# FP_A_TTypeFBTxs.net
KiCad netlist of a schematic drawn in Altium Designer
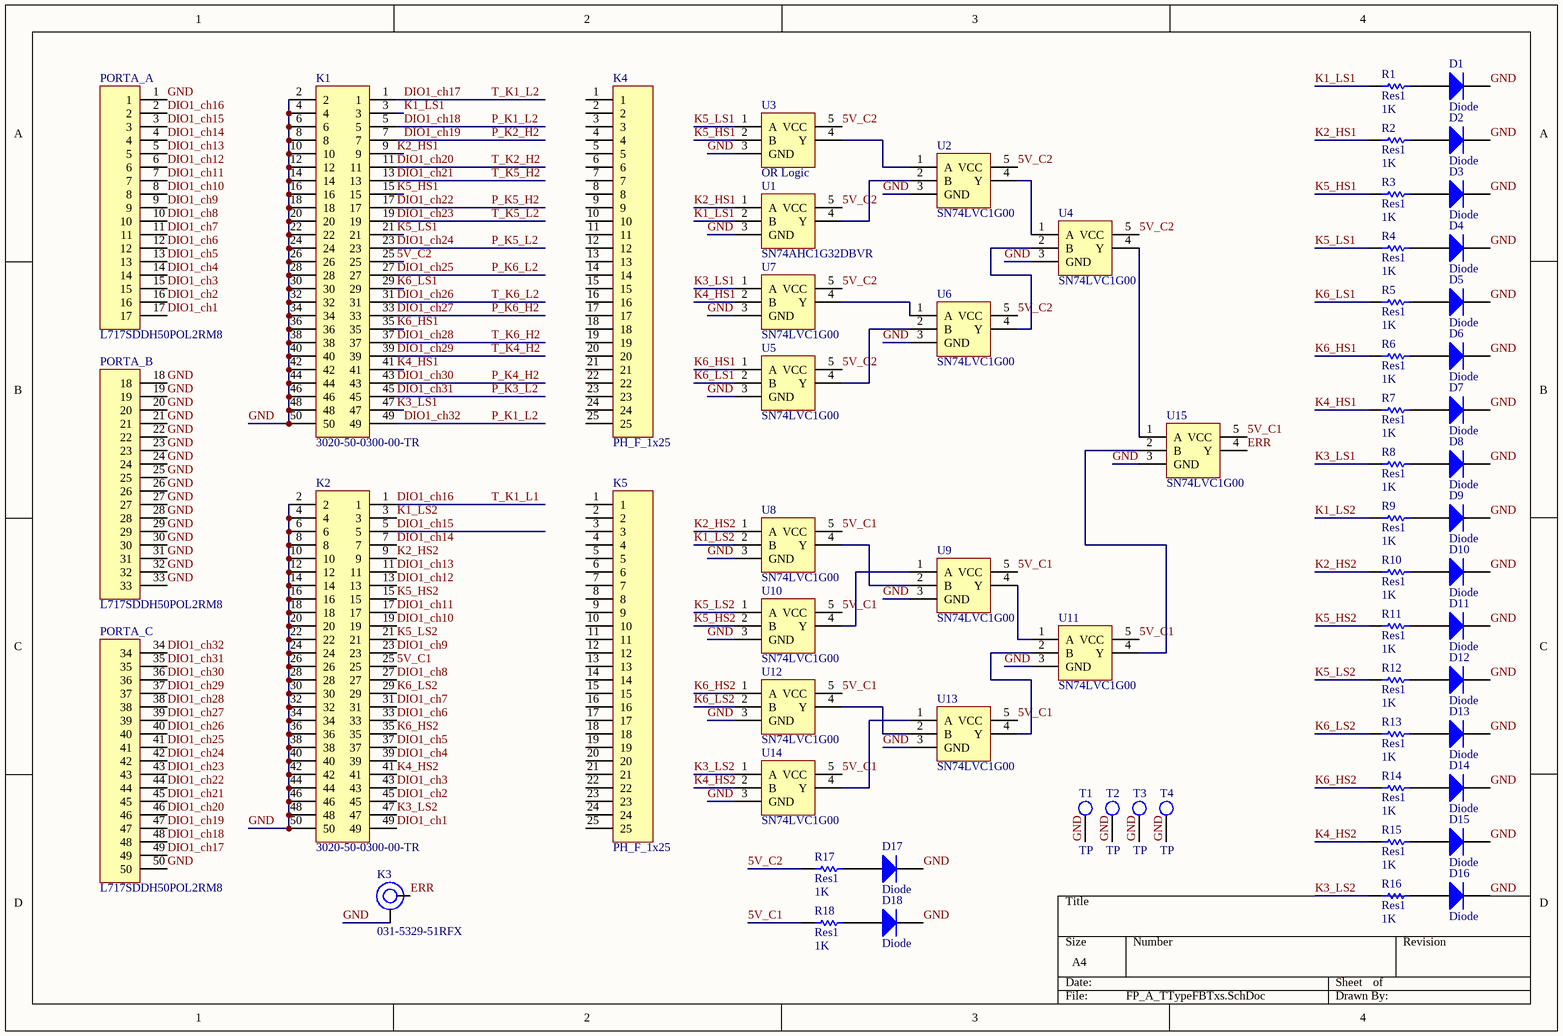
[diagram p0: FP_A_TTypeFBTxs.SchDoc]

(export (version "E")
  (design (tool "Eeschema 10.0.6"))
  (components
    (comp (ref "D1")
      (value "Diode")
      (footprint "0603")
      (description "Default Diode")
      (fields (field (name "PUBLISHER") "Altium Limited"))
      (libsource (lib "Miscellaneous Devices") (part "Diode"))
    )
    (comp (ref "D2")
      (value "Diode")
      (footprint "0603")
      (description "Default Diode")
      (fields (field (name "PUBLISHER") "Altium Limited"))
      (libsource (lib "Miscellaneous Devices") (part "Diode"))
    )
    (comp (ref "D3")
      (value "Diode")
      (footprint "0603")
      (description "Default Diode")
      (fields (field (name "PUBLISHER") "Altium Limited"))
      (libsource (lib "Miscellaneous Devices") (part "Diode"))
    )
    (comp (ref "D4")
      (value "Diode")
      (footprint "0603")
      (description "Default Diode")
      (fields (field (name "PUBLISHER") "Altium Limited"))
      (libsource (lib "Miscellaneous Devices") (part "Diode"))
    )
    (comp (ref "D5")
      (value "Diode")
      (footprint "0603")
      (description "Default Diode")
      (fields (field (name "PUBLISHER") "Altium Limited"))
      (libsource (lib "Miscellaneous Devices") (part "Diode"))
    )
    (comp (ref "D6")
      (value "Diode")
      (footprint "0603")
      (description "Default Diode")
      (fields (field (name "PUBLISHER") "Altium Limited"))
      (libsource (lib "Miscellaneous Devices") (part "Diode"))
    )
    (comp (ref "D7")
      (value "Diode")
      (footprint "0603")
      (description "Default Diode")
      (fields (field (name "PUBLISHER") "Altium Limited"))
      (libsource (lib "Miscellaneous Devices") (part "Diode"))
    )
    (comp (ref "D8")
      (value "Diode")
      (footprint "0603")
      (description "Default Diode")
      (fields (field (name "PUBLISHER") "Altium Limited"))
      (libsource (lib "Miscellaneous Devices") (part "Diode"))
    )
    (comp (ref "D9")
      (value "Diode")
      (footprint "0603")
      (description "Default Diode")
      (fields (field (name "PUBLISHER") "Altium Limited"))
      (libsource (lib "Miscellaneous Devices") (part "Diode"))
    )
    (comp (ref "D10")
      (value "Diode")
      (footprint "0603")
      (description "Default Diode")
      (fields (field (name "PUBLISHER") "Altium Limited"))
      (libsource (lib "Miscellaneous Devices") (part "Diode"))
    )
    (comp (ref "D11")
      (value "Diode")
      (footprint "0603")
      (description "Default Diode")
      (fields (field (name "PUBLISHER") "Altium Limited"))
      (libsource (lib "Miscellaneous Devices") (part "Diode"))
    )
    (comp (ref "D12")
      (value "Diode")
      (footprint "0603")
      (description "Default Diode")
      (fields (field (name "PUBLISHER") "Altium Limited"))
      (libsource (lib "Miscellaneous Devices") (part "Diode"))
    )
    (comp (ref "D13")
      (value "Diode")
      (footprint "0603")
      (description "Default Diode")
      (fields (field (name "PUBLISHER") "Altium Limited"))
      (libsource (lib "Miscellaneous Devices") (part "Diode"))
    )
    (comp (ref "D14")
      (value "Diode")
      (footprint "0603")
      (description "Default Diode")
      (fields (field (name "PUBLISHER") "Altium Limited"))
      (libsource (lib "Miscellaneous Devices") (part "Diode"))
    )
    (comp (ref "D15")
      (value "Diode")
      (footprint "0603")
      (description "Default Diode")
      (fields (field (name "PUBLISHER") "Altium Limited"))
      (libsource (lib "Miscellaneous Devices") (part "Diode"))
    )
    (comp (ref "D16")
      (value "Diode")
      (footprint "0603")
      (description "Default Diode")
      (fields (field (name "PUBLISHER") "Altium Limited"))
      (libsource (lib "Miscellaneous Devices") (part "Diode"))
    )
    (comp (ref "D17")
      (value "Diode")
      (footprint "0603")
      (description "Default Diode")
      (fields (field (name "PUBLISHER") "Altium Limited"))
      (libsource (lib "Miscellaneous Devices") (part "Diode"))
    )
    (comp (ref "D18")
      (value "Diode")
      (footprint "0603")
      (description "Default Diode")
      (fields (field (name "PUBLISHER") "Altium Limited"))
      (libsource (lib "Miscellaneous Devices") (part "Diode"))
    )
    (comp (ref "K1")
      (value "3020-50-0300-00-TR")
      (footprint "IDC_2x50")
      (libsource (lib "Schlib1") (part "3020-50-0300-00-TR"))
    )
    (comp (ref "K2")
      (value "3020-50-0300-00-TR")
      (footprint "IDC_2x50")
      (libsource (lib "Schlib1") (part "3020-50-0300-00-TR"))
    )
    (comp (ref "K3")
      (value "031-5329-51RFX")
      (footprint "BNC_PCB")
      (libsource (lib "Schlib1") (part "031-5329-51RFX"))
    )
    (comp (ref "K4")
      (value "PH_F_1x25")
      (footprint "PH_F_1x25")
      (libsource (lib "Schlib1") (part "PH_F_1x25"))
    )
    (comp (ref "K5")
      (value "PH_F_1x25")
      (footprint "PH_F_1x25")
      (libsource (lib "Schlib1") (part "PH_F_1x25"))
    )
    (comp (ref "PORTA_")
      (value "L717SDDH50POL2RM8")
      (footprint "L717SDDH50POL2RM8")
      (libsource (lib "Schlib1") (part "L717SDDH50POL2RM8"))
    )
    (comp (ref "R1")
      (value "Res1")
      (footprint "0603")
      (description "Resistor")
      (fields (field (name "ALTIUM_VALUE") "1K") (field (name "PUBLISHER") "Altium Limited"))
      (libsource (lib "Miscellaneous Devices") (part "Res1"))
    )
    (comp (ref "R2")
      (value "Res1")
      (footprint "0603")
      (description "Resistor")
      (fields (field (name "ALTIUM_VALUE") "1K") (field (name "PUBLISHER") "Altium Limited"))
      (libsource (lib "Miscellaneous Devices") (part "Res1"))
    )
    (comp (ref "R3")
      (value "Res1")
      (footprint "0603")
      (description "Resistor")
      (fields (field (name "ALTIUM_VALUE") "1K") (field (name "PUBLISHER") "Altium Limited"))
      (libsource (lib "Miscellaneous Devices") (part "Res1"))
    )
    (comp (ref "R4")
      (value "Res1")
      (footprint "0603")
      (description "Resistor")
      (fields (field (name "ALTIUM_VALUE") "1K") (field (name "PUBLISHER") "Altium Limited"))
      (libsource (lib "Miscellaneous Devices") (part "Res1"))
    )
    (comp (ref "R5")
      (value "Res1")
      (footprint "0603")
      (description "Resistor")
      (fields (field (name "ALTIUM_VALUE") "1K") (field (name "PUBLISHER") "Altium Limited"))
      (libsource (lib "Miscellaneous Devices") (part "Res1"))
    )
    (comp (ref "R6")
      (value "Res1")
      (footprint "0603")
      (description "Resistor")
      (fields (field (name "ALTIUM_VALUE") "1K") (field (name "PUBLISHER") "Altium Limited"))
      (libsource (lib "Miscellaneous Devices") (part "Res1"))
    )
    (comp (ref "R7")
      (value "Res1")
      (footprint "0603")
      (description "Resistor")
      (fields (field (name "ALTIUM_VALUE") "1K") (field (name "PUBLISHER") "Altium Limited"))
      (libsource (lib "Miscellaneous Devices") (part "Res1"))
    )
    (comp (ref "R8")
      (value "Res1")
      (footprint "0603")
      (description "Resistor")
      (fields (field (name "ALTIUM_VALUE") "1K") (field (name "PUBLISHER") "Altium Limited"))
      (libsource (lib "Miscellaneous Devices") (part "Res1"))
    )
    (comp (ref "R9")
      (value "Res1")
      (footprint "0603")
      (description "Resistor")
      (fields (field (name "ALTIUM_VALUE") "1K") (field (name "PUBLISHER") "Altium Limited"))
      (libsource (lib "Miscellaneous Devices") (part "Res1"))
    )
    (comp (ref "R10")
      (value "Res1")
      (footprint "0603")
      (description "Resistor")
      (fields (field (name "ALTIUM_VALUE") "1K") (field (name "PUBLISHER") "Altium Limited"))
      (libsource (lib "Miscellaneous Devices") (part "Res1"))
    )
    (comp (ref "R11")
      (value "Res1")
      (footprint "0603")
      (description "Resistor")
      (fields (field (name "ALTIUM_VALUE") "1K") (field (name "PUBLISHER") "Altium Limited"))
      (libsource (lib "Miscellaneous Devices") (part "Res1"))
    )
    (comp (ref "R12")
      (value "Res1")
      (footprint "0603")
      (description "Resistor")
      (fields (field (name "ALTIUM_VALUE") "1K") (field (name "PUBLISHER") "Altium Limited"))
      (libsource (lib "Miscellaneous Devices") (part "Res1"))
    )
    (comp (ref "R13")
      (value "Res1")
      (footprint "0603")
      (description "Resistor")
      (fields (field (name "ALTIUM_VALUE") "1K") (field (name "PUBLISHER") "Altium Limited"))
      (libsource (lib "Miscellaneous Devices") (part "Res1"))
    )
    (comp (ref "R14")
      (value "Res1")
      (footprint "0603")
      (description "Resistor")
      (fields (field (name "ALTIUM_VALUE") "1K") (field (name "PUBLISHER") "Altium Limited"))
      (libsource (lib "Miscellaneous Devices") (part "Res1"))
    )
    (comp (ref "R15")
      (value "Res1")
      (footprint "0603")
      (description "Resistor")
      (fields (field (name "ALTIUM_VALUE") "1K") (field (name "PUBLISHER") "Altium Limited"))
      (libsource (lib "Miscellaneous Devices") (part "Res1"))
    )
    (comp (ref "R16")
      (value "Res1")
      (footprint "0603")
      (description "Resistor")
      (fields (field (name "ALTIUM_VALUE") "1K") (field (name "PUBLISHER") "Altium Limited"))
      (libsource (lib "Miscellaneous Devices") (part "Res1"))
    )
    (comp (ref "R17")
      (value "Res1")
      (footprint "0603")
      (description "Resistor")
      (fields (field (name "ALTIUM_VALUE") "1K") (field (name "PUBLISHER") "Altium Limited"))
      (libsource (lib "Miscellaneous Devices") (part "Res1"))
    )
    (comp (ref "R18")
      (value "Res1")
      (footprint "0603")
      (description "Resistor")
      (fields (field (name "ALTIUM_VALUE") "1K") (field (name "PUBLISHER") "Altium Limited"))
      (libsource (lib "Miscellaneous Devices") (part "Res1"))
    )
    (comp (ref "T1") (value "TP") (footprint "TP") (libsource (lib "Schlib1") (part "TP")))
    (comp (ref "T2") (value "TP") (footprint "TP") (libsource (lib "Schlib1") (part "TP")))
    (comp (ref "T3") (value "TP") (footprint "TP") (libsource (lib "Schlib1") (part "TP")))
    (comp (ref "T4") (value "TP") (footprint "TP") (libsource (lib "Schlib1") (part "TP")))
    (comp (ref "U1")
      (value "SN74AHC1G32DBVR")
      (footprint "sot23")
      (libsource (lib "Schlib1") (part "SN74AHC1G32DBVR"))
    )
    (comp (ref "U2")
      (value "SN74LVC1G00")
      (footprint "sot23")
      (libsource (lib "Schlib1") (part "SN74LVC1G00"))
    )
    (comp (ref "U3")
      (value "OR Logic")
      (footprint "sot23")
      (libsource (lib "Schlib1") (part "SN74AHC1G32DBVR"))
    )
    (comp (ref "U4")
      (value "SN74LVC1G00")
      (footprint "sot23")
      (libsource (lib "Schlib1") (part "SN74LVC1G00"))
    )
    (comp (ref "U5")
      (value "SN74LVC1G00")
      (footprint "sot23")
      (libsource (lib "Schlib1") (part "SN74LVC1G00"))
    )
    (comp (ref "U6")
      (value "SN74LVC1G00")
      (footprint "sot23")
      (libsource (lib "Schlib1") (part "SN74LVC1G00"))
    )
    (comp (ref "U7")
      (value "SN74LVC1G00")
      (footprint "sot23")
      (libsource (lib "Schlib1") (part "SN74LVC1G00"))
    )
    (comp (ref "U8")
      (value "SN74LVC1G00")
      (footprint "sot23")
      (libsource (lib "Schlib1") (part "SN74LVC1G00"))
    )
    (comp (ref "U9")
      (value "SN74LVC1G00")
      (footprint "sot23")
      (libsource (lib "Schlib1") (part "SN74LVC1G00"))
    )
    (comp (ref "U10")
      (value "SN74LVC1G00")
      (footprint "sot23")
      (libsource (lib "Schlib1") (part "SN74LVC1G00"))
    )
    (comp (ref "U11")
      (value "SN74LVC1G00")
      (footprint "sot23")
      (libsource (lib "Schlib1") (part "SN74LVC1G00"))
    )
    (comp (ref "U12")
      (value "SN74LVC1G00")
      (footprint "sot23")
      (libsource (lib "Schlib1") (part "SN74LVC1G00"))
    )
    (comp (ref "U13")
      (value "SN74LVC1G00")
      (footprint "sot23")
      (libsource (lib "Schlib1") (part "SN74LVC1G00"))
    )
    (comp (ref "U14")
      (value "SN74LVC1G00")
      (footprint "sot23")
      (libsource (lib "Schlib1") (part "SN74LVC1G00"))
    )
    (comp (ref "U15")
      (value "SN74LVC1G00")
      (footprint "sot23")
      (libsource (lib "Schlib1") (part "SN74LVC1G00"))
    )
  )
  (nets
    (net (code "1") (name "/5V_C1") (class "Default")
      (node (ref "K2") (pin "25") (pinfunction "25_25") (pintype "passive"))
      (node (ref "R18") (pin "2") (pinfunction "2_2") (pintype "passive"))
      (node (ref "U10") (pin "5") (pinfunction "VCC_5") (pintype "passive"))
      (node (ref "U11") (pin "5") (pinfunction "VCC_5") (pintype "passive"))
      (node (ref "U12") (pin "5") (pinfunction "VCC_5") (pintype "passive"))
      (node (ref "U13") (pin "5") (pinfunction "VCC_5") (pintype "passive"))
      (node (ref "U14") (pin "5") (pinfunction "VCC_5") (pintype "passive"))
      (node (ref "U15") (pin "5") (pinfunction "VCC_5") (pintype "passive"))
      (node (ref "U8") (pin "5") (pinfunction "VCC_5") (pintype "passive"))
      (node (ref "U9") (pin "5") (pinfunction "VCC_5") (pintype "passive"))
    )
    (net (code "2") (name "/5V_C2") (class "Default")
      (node (ref "K1") (pin "25") (pinfunction "25_25") (pintype "passive"))
      (node (ref "R17") (pin "2") (pinfunction "2_2") (pintype "passive"))
      (node (ref "U1") (pin "5") (pinfunction "VCC_5") (pintype "passive"))
      (node (ref "U2") (pin "5") (pinfunction "VCC_5") (pintype "passive"))
      (node (ref "U3") (pin "5") (pinfunction "VCC_5") (pintype "passive"))
      (node (ref "U4") (pin "5") (pinfunction "VCC_5") (pintype "passive"))
      (node (ref "U5") (pin "5") (pinfunction "VCC_5") (pintype "passive"))
      (node (ref "U6") (pin "5") (pinfunction "VCC_5") (pintype "passive"))
      (node (ref "U7") (pin "5") (pinfunction "VCC_5") (pintype "passive"))
    )
    (net (code "3") (name "/DIO1_ch1") (class "Default")
      (node (ref "K2") (pin "49") (pinfunction "49_49") (pintype "passive"))
      (node (ref "PORTA_") (pin "17") (pinfunction "17_17") (pintype "passive"))
    )
    (net (code "4") (name "/DIO1_ch2") (class "Default")
      (node (ref "K2") (pin "45") (pinfunction "45_45") (pintype "passive"))
      (node (ref "PORTA_") (pin "16") (pinfunction "16_16") (pintype "passive"))
    )
    (net (code "5") (name "/DIO1_ch3") (class "Default")
      (node (ref "K2") (pin "43") (pinfunction "43_43") (pintype "passive"))
      (node (ref "PORTA_") (pin "15") (pinfunction "15_15") (pintype "passive"))
    )
    (net (code "6") (name "/DIO1_ch4") (class "Default")
      (node (ref "K2") (pin "39") (pinfunction "39_39") (pintype "passive"))
      (node (ref "PORTA_") (pin "14") (pinfunction "14_14") (pintype "passive"))
    )
    (net (code "7") (name "/DIO1_ch5") (class "Default")
      (node (ref "K2") (pin "37") (pinfunction "37_37") (pintype "passive"))
      (node (ref "PORTA_") (pin "13") (pinfunction "13_13") (pintype "passive"))
    )
    (net (code "8") (name "/DIO1_ch6") (class "Default")
      (node (ref "K2") (pin "33") (pinfunction "33_33") (pintype "passive"))
      (node (ref "PORTA_") (pin "12") (pinfunction "12_12") (pintype "passive"))
    )
    (net (code "9") (name "/DIO1_ch7") (class "Default")
      (node (ref "K2") (pin "31") (pinfunction "31_31") (pintype "passive"))
      (node (ref "PORTA_") (pin "11") (pinfunction "11_11") (pintype "passive"))
    )
    (net (code "10") (name "/DIO1_ch8") (class "Default")
      (node (ref "K2") (pin "27") (pinfunction "27_27") (pintype "passive"))
      (node (ref "PORTA_") (pin "10") (pinfunction "10_10") (pintype "passive"))
    )
    (net (code "11") (name "/DIO1_ch9") (class "Default")
      (node (ref "K2") (pin "23") (pinfunction "23_23") (pintype "passive"))
      (node (ref "PORTA_") (pin "9") (pinfunction "9_9") (pintype "passive"))
    )
    (net (code "12") (name "/DIO1_ch10") (class "Default")
      (node (ref "K2") (pin "19") (pinfunction "19_19") (pintype "passive"))
      (node (ref "PORTA_") (pin "8") (pinfunction "8_8") (pintype "passive"))
    )
    (net (code "13") (name "/DIO1_ch11") (class "Default")
      (node (ref "K2") (pin "17") (pinfunction "17_17") (pintype "passive"))
      (node (ref "PORTA_") (pin "7") (pinfunction "7_7") (pintype "passive"))
    )
    (net (code "14") (name "/DIO1_ch12") (class "Default")
      (node (ref "K2") (pin "13") (pinfunction "13_13") (pintype "passive"))
      (node (ref "PORTA_") (pin "6") (pinfunction "6_6") (pintype "passive"))
    )
    (net (code "15") (name "/DIO1_ch13") (class "Default")
      (node (ref "K2") (pin "11") (pinfunction "11_11") (pintype "passive"))
      (node (ref "PORTA_") (pin "5") (pinfunction "5_5") (pintype "passive"))
    )
    (net (code "16") (name "/DIO1_ch14") (class "Default")
      (node (ref "K2") (pin "7") (pinfunction "7_7") (pintype "passive"))
      (node (ref "PORTA_") (pin "4") (pinfunction "4_4") (pintype "passive"))
    )
    (net (code "17") (name "/DIO1_ch15") (class "Default")
      (node (ref "K2") (pin "5") (pinfunction "5_5") (pintype "passive"))
      (node (ref "PORTA_") (pin "3") (pinfunction "3_3") (pintype "passive"))
    )
    (net (code "18") (name "/DIO1_ch16") (class "Default")
      (node (ref "K2") (pin "1") (pinfunction "1_1") (pintype "passive"))
      (node (ref "PORTA_") (pin "2") (pinfunction "2_2") (pintype "passive"))
    )
    (net (code "19") (name "/DIO1_ch17") (class "Default")
      (node (ref "K1") (pin "1") (pinfunction "1_1") (pintype "passive"))
      (node (ref "PORTA_") (pin "49") (pinfunction "49_49") (pintype "passive"))
    )
    (net (code "20") (name "/DIO1_ch18") (class "Default")
      (node (ref "K1") (pin "49") (pinfunction "49_49") (pintype "passive"))
      (node (ref "K1") (pin "5") (pinfunction "5_5") (pintype "passive"))
      (node (ref "PORTA_") (pin "34") (pinfunction "34_34") (pintype "passive"))
      (node (ref "PORTA_") (pin "48") (pinfunction "48_48") (pintype "passive"))
    )
    (net (code "21") (name "/DIO1_ch19") (class "Default")
      (node (ref "K1") (pin "7") (pinfunction "7_7") (pintype "passive"))
      (node (ref "PORTA_") (pin "47") (pinfunction "47_47") (pintype "passive"))
    )
    (net (code "22") (name "/DIO1_ch20") (class "Default")
      (node (ref "K1") (pin "11") (pinfunction "11_11") (pintype "passive"))
      (node (ref "PORTA_") (pin "46") (pinfunction "46_46") (pintype "passive"))
    )
    (net (code "23") (name "/DIO1_ch21") (class "Default")
      (node (ref "K1") (pin "13") (pinfunction "13_13") (pintype "passive"))
      (node (ref "PORTA_") (pin "45") (pinfunction "45_45") (pintype "passive"))
    )
    (net (code "24") (name "/DIO1_ch22") (class "Default")
      (node (ref "K1") (pin "17") (pinfunction "17_17") (pintype "passive"))
      (node (ref "PORTA_") (pin "44") (pinfunction "44_44") (pintype "passive"))
    )
    (net (code "25") (name "/DIO1_ch23") (class "Default")
      (node (ref "K1") (pin "19") (pinfunction "19_19") (pintype "passive"))
      (node (ref "PORTA_") (pin "43") (pinfunction "43_43") (pintype "passive"))
    )
    (net (code "26") (name "/DIO1_ch24") (class "Default")
      (node (ref "K1") (pin "23") (pinfunction "23_23") (pintype "passive"))
      (node (ref "PORTA_") (pin "42") (pinfunction "42_42") (pintype "passive"))
    )
    (net (code "27") (name "/DIO1_ch25") (class "Default")
      (node (ref "K1") (pin "27") (pinfunction "27_27") (pintype "passive"))
      (node (ref "PORTA_") (pin "41") (pinfunction "41_41") (pintype "passive"))
    )
    (net (code "28") (name "/DIO1_ch26") (class "Default")
      (node (ref "K1") (pin "31") (pinfunction "31_31") (pintype "passive"))
      (node (ref "PORTA_") (pin "40") (pinfunction "40_40") (pintype "passive"))
    )
    (net (code "29") (name "/DIO1_ch27") (class "Default")
      (node (ref "K1") (pin "33") (pinfunction "33_33") (pintype "passive"))
      (node (ref "PORTA_") (pin "39") (pinfunction "39_39") (pintype "passive"))
    )
    (net (code "30") (name "/DIO1_ch28") (class "Default")
      (node (ref "K1") (pin "37") (pinfunction "37_37") (pintype "passive"))
      (node (ref "PORTA_") (pin "38") (pinfunction "38_38") (pintype "passive"))
    )
    (net (code "31") (name "/DIO1_ch29") (class "Default")
      (node (ref "K1") (pin "39") (pinfunction "39_39") (pintype "passive"))
      (node (ref "PORTA_") (pin "37") (pinfunction "37_37") (pintype "passive"))
    )
    (net (code "32") (name "/DIO1_ch30") (class "Default")
      (node (ref "K1") (pin "43") (pinfunction "43_43") (pintype "passive"))
      (node (ref "PORTA_") (pin "36") (pinfunction "36_36") (pintype "passive"))
    )
    (net (code "33") (name "/DIO1_ch31") (class "Default")
      (node (ref "K1") (pin "45") (pinfunction "45_45") (pintype "passive"))
      (node (ref "PORTA_") (pin "35") (pinfunction "35_35") (pintype "passive"))
    )
    (net (code "34") (name "/ERR") (class "Default")
      (node (ref "K3") (pin "1") (pinfunction "1_1") (pintype "passive"))
      (node (ref "U15") (pin "4") (pinfunction "Y_4") (pintype "passive"))
    )
    (net (code "35") (name "/GND") (class "Default")
      (node (ref "D1") (pin "2") (pinfunction "K_2") (pintype "passive"))
      (node (ref "D10") (pin "2") (pinfunction "K_2") (pintype "passive"))
      (node (ref "D11") (pin "2") (pinfunction "K_2") (pintype "passive"))
      (node (ref "D12") (pin "2") (pinfunction "K_2") (pintype "passive"))
      (node (ref "D13") (pin "2") (pinfunction "K_2") (pintype "passive"))
      (node (ref "D14") (pin "2") (pinfunction "K_2") (pintype "passive"))
      (node (ref "D15") (pin "2") (pinfunction "K_2") (pintype "passive"))
      (node (ref "D16") (pin "2") (pinfunction "K_2") (pintype "passive"))
      (node (ref "D17") (pin "2") (pinfunction "K_2") (pintype "passive"))
      (node (ref "D18") (pin "2") (pinfunction "K_2") (pintype "passive"))
      (node (ref "D2") (pin "2") (pinfunction "K_2") (pintype "passive"))
      (node (ref "D3") (pin "2") (pinfunction "K_2") (pintype "passive"))
      (node (ref "D4") (pin "2") (pinfunction "K_2") (pintype "passive"))
      (node (ref "D5") (pin "2") (pinfunction "K_2") (pintype "passive"))
      (node (ref "D6") (pin "2") (pinfunction "K_2") (pintype "passive"))
      (node (ref "D7") (pin "2") (pinfunction "K_2") (pintype "passive"))
      (node (ref "D8") (pin "2") (pinfunction "K_2") (pintype "passive"))
      (node (ref "D9") (pin "2") (pinfunction "K_2") (pintype "passive"))
      (node (ref "K1") (pin "10") (pinfunction "10_10") (pintype "passive"))
      (node (ref "K1") (pin "12") (pinfunction "12_12") (pintype "passive"))
      (node (ref "K1") (pin "14") (pinfunction "14_14") (pintype "passive"))
      (node (ref "K1") (pin "16") (pinfunction "16_16") (pintype "passive"))
      (node (ref "K1") (pin "18") (pinfunction "18_18") (pintype "passive"))
      (node (ref "K1") (pin "2") (pinfunction "2_2") (pintype "passive"))
      (node (ref "K1") (pin "20") (pinfunction "20_20") (pintype "passive"))
      (node (ref "K1") (pin "22") (pinfunction "22_22") (pintype "passive"))
      (node (ref "K1") (pin "24") (pinfunction "24_24") (pintype "passive"))
      (node (ref "K1") (pin "26") (pinfunction "26_26") (pintype "passive"))
      (node (ref "K1") (pin "28") (pinfunction "28_28") (pintype "passive"))
      (node (ref "K1") (pin "30") (pinfunction "30_30") (pintype "passive"))
      (node (ref "K1") (pin "32") (pinfunction "32_32") (pintype "passive"))
      (node (ref "K1") (pin "34") (pinfunction "34_34") (pintype "passive"))
      (node (ref "K1") (pin "36") (pinfunction "36_36") (pintype "passive"))
      (node (ref "K1") (pin "38") (pinfunction "38_38") (pintype "passive"))
      (node (ref "K1") (pin "4") (pinfunction "4_4") (pintype "passive"))
      (node (ref "K1") (pin "40") (pinfunction "40_40") (pintype "passive"))
      (node (ref "K1") (pin "42") (pinfunction "42_42") (pintype "passive"))
      (node (ref "K1") (pin "44") (pinfunction "44_44") (pintype "passive"))
      (node (ref "K1") (pin "46") (pinfunction "46_46") (pintype "passive"))
      (node (ref "K1") (pin "48") (pinfunction "48_48") (pintype "passive"))
      (node (ref "K1") (pin "50") (pinfunction "50_50") (pintype "passive"))
      (node (ref "K1") (pin "6") (pinfunction "6_6") (pintype "passive"))
      (node (ref "K1") (pin "8") (pinfunction "8_8") (pintype "passive"))
      (node (ref "K2") (pin "10") (pinfunction "10_10") (pintype "passive"))
      (node (ref "K2") (pin "12") (pinfunction "12_12") (pintype "passive"))
      (node (ref "K2") (pin "14") (pinfunction "14_14") (pintype "passive"))
      (node (ref "K2") (pin "16") (pinfunction "16_16") (pintype "passive"))
      (node (ref "K2") (pin "18") (pinfunction "18_18") (pintype "passive"))
      (node (ref "K2") (pin "2") (pinfunction "2_2") (pintype "passive"))
      (node (ref "K2") (pin "20") (pinfunction "20_20") (pintype "passive"))
      (node (ref "K2") (pin "22") (pinfunction "22_22") (pintype "passive"))
      (node (ref "K2") (pin "24") (pinfunction "24_24") (pintype "passive"))
      (node (ref "K2") (pin "26") (pinfunction "26_26") (pintype "passive"))
      (node (ref "K2") (pin "28") (pinfunction "28_28") (pintype "passive"))
      (node (ref "K2") (pin "30") (pinfunction "30_30") (pintype "passive"))
      (node (ref "K2") (pin "32") (pinfunction "32_32") (pintype "passive"))
      (node (ref "K2") (pin "34") (pinfunction "34_34") (pintype "passive"))
      (node (ref "K2") (pin "36") (pinfunction "36_36") (pintype "passive"))
      (node (ref "K2") (pin "38") (pinfunction "38_38") (pintype "passive"))
      (node (ref "K2") (pin "4") (pinfunction "4_4") (pintype "passive"))
      (node (ref "K2") (pin "40") (pinfunction "40_40") (pintype "passive"))
      (node (ref "K2") (pin "42") (pinfunction "42_42") (pintype "passive"))
      (node (ref "K2") (pin "44") (pinfunction "44_44") (pintype "passive"))
      (node (ref "K2") (pin "46") (pinfunction "46_46") (pintype "passive"))
      (node (ref "K2") (pin "48") (pinfunction "48_48") (pintype "passive"))
      (node (ref "K2") (pin "50") (pinfunction "50_50") (pintype "passive"))
      (node (ref "K2") (pin "6") (pinfunction "6_6") (pintype "passive"))
      (node (ref "K2") (pin "8") (pinfunction "8_8") (pintype "passive"))
      (node (ref "K3") (pin "2") (pinfunction "2_2") (pintype "passive"))
      (node (ref "PORTA_") (pin "1") (pinfunction "1_1") (pintype "passive"))
      (node (ref "PORTA_") (pin "18") (pinfunction "18_18") (pintype "passive"))
      (node (ref "PORTA_") (pin "19") (pinfunction "19_19") (pintype "passive"))
      (node (ref "PORTA_") (pin "20") (pinfunction "20_20") (pintype "passive"))
      (node (ref "PORTA_") (pin "21") (pinfunction "21_21") (pintype "passive"))
      (node (ref "PORTA_") (pin "22") (pinfunction "22_22") (pintype "passive"))
      (node (ref "PORTA_") (pin "23") (pinfunction "23_23") (pintype "passive"))
      (node (ref "PORTA_") (pin "24") (pinfunction "24_24") (pintype "passive"))
      (node (ref "PORTA_") (pin "25") (pinfunction "25_25") (pintype "passive"))
      (node (ref "PORTA_") (pin "26") (pinfunction "26_26") (pintype "passive"))
      (node (ref "PORTA_") (pin "27") (pinfunction "27_27") (pintype "passive"))
      (node (ref "PORTA_") (pin "28") (pinfunction "28_28") (pintype "passive"))
      (node (ref "PORTA_") (pin "29") (pinfunction "29_29") (pintype "passive"))
      (node (ref "PORTA_") (pin "30") (pinfunction "30_30") (pintype "passive"))
      (node (ref "PORTA_") (pin "31") (pinfunction "31_31") (pintype "passive"))
      (node (ref "PORTA_") (pin "32") (pinfunction "32_32") (pintype "passive"))
      (node (ref "PORTA_") (pin "33") (pinfunction "33_33") (pintype "passive"))
      (node (ref "PORTA_") (pin "50") (pinfunction "50_50") (pintype "passive"))
      (node (ref "T1") (pin "1") (pinfunction "1_1") (pintype "passive"))
      (node (ref "T2") (pin "1") (pinfunction "1_1") (pintype "passive"))
      (node (ref "T3") (pin "1") (pinfunction "1_1") (pintype "passive"))
      (node (ref "T4") (pin "1") (pinfunction "1_1") (pintype "passive"))
      (node (ref "U1") (pin "3") (pinfunction "GND_3") (pintype "passive"))
      (node (ref "U10") (pin "3") (pinfunction "GND_3") (pintype "passive"))
      (node (ref "U11") (pin "3") (pinfunction "GND_3") (pintype "passive"))
      (node (ref "U12") (pin "3") (pinfunction "GND_3") (pintype "passive"))
      (node (ref "U13") (pin "3") (pinfunction "GND_3") (pintype "passive"))
      (node (ref "U14") (pin "3") (pinfunction "GND_3") (pintype "passive"))
      (node (ref "U15") (pin "3") (pinfunction "GND_3") (pintype "passive"))
      (node (ref "U2") (pin "3") (pinfunction "GND_3") (pintype "passive"))
      (node (ref "U3") (pin "3") (pinfunction "GND_3") (pintype "passive"))
      (node (ref "U4") (pin "3") (pinfunction "GND_3") (pintype "passive"))
      (node (ref "U5") (pin "3") (pinfunction "GND_3") (pintype "passive"))
      (node (ref "U6") (pin "3") (pinfunction "GND_3") (pintype "passive"))
      (node (ref "U7") (pin "3") (pinfunction "GND_3") (pintype "passive"))
      (node (ref "U8") (pin "3") (pinfunction "GND_3") (pintype "passive"))
      (node (ref "U9") (pin "3") (pinfunction "GND_3") (pintype "passive"))
    )
    (net (code "36") (name "/K1_LS1") (class "Default")
      (node (ref "K1") (pin "3") (pinfunction "3_3") (pintype "passive"))
      (node (ref "R1") (pin "2") (pinfunction "2_2") (pintype "passive"))
      (node (ref "U1") (pin "2") (pinfunction "B_2") (pintype "passive"))
    )
    (net (code "37") (name "/K1_LS2") (class "Default")
      (node (ref "K2") (pin "3") (pinfunction "3_3") (pintype "passive"))
      (node (ref "R9") (pin "2") (pinfunction "2_2") (pintype "passive"))
      (node (ref "U8") (pin "2") (pinfunction "B_2") (pintype "passive"))
    )
    (net (code "38") (name "/K2_HS1") (class "Default")
      (node (ref "K1") (pin "9") (pinfunction "9_9") (pintype "passive"))
      (node (ref "R2") (pin "2") (pinfunction "2_2") (pintype "passive"))
      (node (ref "U1") (pin "1") (pinfunction "A_1") (pintype "passive"))
    )
    (net (code "39") (name "/K2_HS2") (class "Default")
      (node (ref "K2") (pin "9") (pinfunction "9_9") (pintype "passive"))
      (node (ref "R10") (pin "2") (pinfunction "2_2") (pintype "passive"))
      (node (ref "U8") (pin "1") (pinfunction "A_1") (pintype "passive"))
    )
    (net (code "40") (name "/K3_LS1") (class "Default")
      (node (ref "K1") (pin "47") (pinfunction "47_47") (pintype "passive"))
      (node (ref "R8") (pin "2") (pinfunction "2_2") (pintype "passive"))
      (node (ref "U7") (pin "1") (pinfunction "A_1") (pintype "passive"))
    )
    (net (code "41") (name "/K3_LS2") (class "Default")
      (node (ref "K2") (pin "47") (pinfunction "47_47") (pintype "passive"))
      (node (ref "R16") (pin "2") (pinfunction "2_2") (pintype "passive"))
      (node (ref "U14") (pin "1") (pinfunction "A_1") (pintype "passive"))
    )
    (net (code "42") (name "/K4_HS1") (class "Default")
      (node (ref "K1") (pin "41") (pinfunction "41_41") (pintype "passive"))
      (node (ref "R7") (pin "2") (pinfunction "2_2") (pintype "passive"))
      (node (ref "U7") (pin "2") (pinfunction "B_2") (pintype "passive"))
    )
    (net (code "43") (name "/K4_HS2") (class "Default")
      (node (ref "K2") (pin "41") (pinfunction "41_41") (pintype "passive"))
      (node (ref "R15") (pin "2") (pinfunction "2_2") (pintype "passive"))
      (node (ref "U14") (pin "2") (pinfunction "B_2") (pintype "passive"))
    )
    (net (code "44") (name "/K5_HS1") (class "Default")
      (node (ref "K1") (pin "15") (pinfunction "15_15") (pintype "passive"))
      (node (ref "R3") (pin "2") (pinfunction "2_2") (pintype "passive"))
      (node (ref "U3") (pin "2") (pinfunction "B_2") (pintype "passive"))
    )
    (net (code "45") (name "/K5_HS2") (class "Default")
      (node (ref "K2") (pin "15") (pinfunction "15_15") (pintype "passive"))
      (node (ref "R11") (pin "2") (pinfunction "2_2") (pintype "passive"))
      (node (ref "U10") (pin "2") (pinfunction "B_2") (pintype "passive"))
    )
    (net (code "46") (name "/K5_LS1") (class "Default")
      (node (ref "K1") (pin "21") (pinfunction "21_21") (pintype "passive"))
      (node (ref "R4") (pin "2") (pinfunction "2_2") (pintype "passive"))
      (node (ref "U3") (pin "1") (pinfunction "A_1") (pintype "passive"))
    )
    (net (code "47") (name "/K5_LS2") (class "Default")
      (node (ref "K2") (pin "21") (pinfunction "21_21") (pintype "passive"))
      (node (ref "R12") (pin "2") (pinfunction "2_2") (pintype "passive"))
      (node (ref "U10") (pin "1") (pinfunction "A_1") (pintype "passive"))
    )
    (net (code "48") (name "/K6_HS1") (class "Default")
      (node (ref "K1") (pin "35") (pinfunction "35_35") (pintype "passive"))
      (node (ref "R6") (pin "2") (pinfunction "2_2") (pintype "passive"))
      (node (ref "U5") (pin "1") (pinfunction "A_1") (pintype "passive"))
    )
    (net (code "49") (name "/K6_HS2") (class "Default")
      (node (ref "K2") (pin "35") (pinfunction "35_35") (pintype "passive"))
      (node (ref "R14") (pin "2") (pinfunction "2_2") (pintype "passive"))
      (node (ref "U12") (pin "1") (pinfunction "A_1") (pintype "passive"))
    )
    (net (code "50") (name "/K6_LS1") (class "Default")
      (node (ref "K1") (pin "29") (pinfunction "29_29") (pintype "passive"))
      (node (ref "R5") (pin "2") (pinfunction "2_2") (pintype "passive"))
      (node (ref "U5") (pin "2") (pinfunction "B_2") (pintype "passive"))
    )
    (net (code "51") (name "/K6_LS2") (class "Default")
      (node (ref "K2") (pin "29") (pinfunction "29_29") (pintype "passive"))
      (node (ref "R13") (pin "2") (pinfunction "2_2") (pintype "passive"))
      (node (ref "U12") (pin "2") (pinfunction "B_2") (pintype "passive"))
    )
    (net (code "52") (name "Net-(D1-A)") (class "Default")
      (node (ref "D1") (pin "1") (pinfunction "A_1") (pintype "passive"))
      (node (ref "R1") (pin "1") (pinfunction "1_1") (pintype "passive"))
    )
    (net (code "53") (name "Net-(D2-A)") (class "Default")
      (node (ref "D2") (pin "1") (pinfunction "A_1") (pintype "passive"))
      (node (ref "R2") (pin "1") (pinfunction "1_1") (pintype "passive"))
    )
    (net (code "54") (name "Net-(D3-A)") (class "Default")
      (node (ref "D3") (pin "1") (pinfunction "A_1") (pintype "passive"))
      (node (ref "R3") (pin "1") (pinfunction "1_1") (pintype "passive"))
    )
    (net (code "55") (name "Net-(D4-A)") (class "Default")
      (node (ref "D4") (pin "1") (pinfunction "A_1") (pintype "passive"))
      (node (ref "R4") (pin "1") (pinfunction "1_1") (pintype "passive"))
    )
    (net (code "56") (name "Net-(D5-A)") (class "Default")
      (node (ref "D5") (pin "1") (pinfunction "A_1") (pintype "passive"))
      (node (ref "R5") (pin "1") (pinfunction "1_1") (pintype "passive"))
    )
    (net (code "57") (name "Net-(D6-A)") (class "Default")
      (node (ref "D6") (pin "1") (pinfunction "A_1") (pintype "passive"))
      (node (ref "R6") (pin "1") (pinfunction "1_1") (pintype "passive"))
    )
    (net (code "58") (name "Net-(D7-A)") (class "Default")
      (node (ref "D7") (pin "1") (pinfunction "A_1") (pintype "passive"))
      (node (ref "R7") (pin "1") (pinfunction "1_1") (pintype "passive"))
    )
    (net (code "59") (name "Net-(D8-A)") (class "Default")
      (node (ref "D8") (pin "1") (pinfunction "A_1") (pintype "passive"))
      (node (ref "R8") (pin "1") (pinfunction "1_1") (pintype "passive"))
    )
    (net (code "60") (name "Net-(D9-A)") (class "Default")
      (node (ref "D9") (pin "1") (pinfunction "A_1") (pintype "passive"))
      (node (ref "R9") (pin "1") (pinfunction "1_1") (pintype "passive"))
    )
    (net (code "61") (name "Net-(D10-A)") (class "Default")
      (node (ref "D10") (pin "1") (pinfunction "A_1") (pintype "passive"))
      (node (ref "R10") (pin "1") (pinfunction "1_1") (pintype "passive"))
    )
    (net (code "62") (name "Net-(D11-A)") (class "Default")
      (node (ref "D11") (pin "1") (pinfunction "A_1") (pintype "passive"))
      (node (ref "R11") (pin "1") (pinfunction "1_1") (pintype "passive"))
    )
    (net (code "63") (name "Net-(D12-A)") (class "Default")
      (node (ref "D12") (pin "1") (pinfunction "A_1") (pintype "passive"))
      (node (ref "R12") (pin "1") (pinfunction "1_1") (pintype "passive"))
    )
    (net (code "64") (name "Net-(D13-A)") (class "Default")
      (node (ref "D13") (pin "1") (pinfunction "A_1") (pintype "passive"))
      (node (ref "R13") (pin "1") (pinfunction "1_1") (pintype "passive"))
    )
    (net (code "65") (name "Net-(D14-A)") (class "Default")
      (node (ref "D14") (pin "1") (pinfunction "A_1") (pintype "passive"))
      (node (ref "R14") (pin "1") (pinfunction "1_1") (pintype "passive"))
    )
    (net (code "66") (name "Net-(D15-A)") (class "Default")
      (node (ref "D15") (pin "1") (pinfunction "A_1") (pintype "passive"))
      (node (ref "R15") (pin "1") (pinfunction "1_1") (pintype "passive"))
    )
    (net (code "67") (name "Net-(D16-A)") (class "Default")
      (node (ref "D16") (pin "1") (pinfunction "A_1") (pintype "passive"))
      (node (ref "R16") (pin "1") (pinfunction "1_1") (pintype "passive"))
    )
    (net (code "68") (name "Net-(D17-A)") (class "Default")
      (node (ref "D17") (pin "1") (pinfunction "A_1") (pintype "passive"))
      (node (ref "R17") (pin "1") (pinfunction "1_1") (pintype "passive"))
    )
    (net (code "69") (name "Net-(D18-A)") (class "Default")
      (node (ref "D18") (pin "1") (pinfunction "A_1") (pintype "passive"))
      (node (ref "R18") (pin "1") (pinfunction "1_1") (pintype "passive"))
    )
    (net (code "70") (name "Net-(U1-Y)") (class "Default")
      (node (ref "U1") (pin "4") (pinfunction "Y_4") (pintype "passive"))
      (node (ref "U2") (pin "2") (pinfunction "B_2") (pintype "passive"))
    )
    (net (code "71") (name "Net-(U2-A)") (class "Default")
      (node (ref "U2") (pin "1") (pinfunction "A_1") (pintype "passive"))
      (node (ref "U3") (pin "4") (pinfunction "Y_4") (pintype "passive"))
    )
    (net (code "72") (name "Net-(U2-Y)") (class "Default")
      (node (ref "U2") (pin "4") (pinfunction "Y_4") (pintype "passive"))
      (node (ref "U4") (pin "1") (pinfunction "A_1") (pintype "passive"))
    )
    (net (code "73") (name "Net-(U4-B)") (class "Default")
      (node (ref "U4") (pin "2") (pinfunction "B_2") (pintype "passive"))
      (node (ref "U6") (pin "4") (pinfunction "Y_4") (pintype "passive"))
    )
    (net (code "74") (name "Net-(U5-Y)") (class "Default")
      (node (ref "U5") (pin "4") (pinfunction "Y_4") (pintype "passive"))
      (node (ref "U6") (pin "2") (pinfunction "B_2") (pintype "passive"))
    )
    (net (code "75") (name "Net-(U6-A)") (class "Default")
      (node (ref "U6") (pin "1") (pinfunction "A_1") (pintype "passive"))
      (node (ref "U7") (pin "4") (pinfunction "Y_4") (pintype "passive"))
    )
    (net (code "76") (name "Net-(U8-Y)") (class "Default")
      (node (ref "U8") (pin "4") (pinfunction "Y_4") (pintype "passive"))
      (node (ref "U9") (pin "2") (pinfunction "B_2") (pintype "passive"))
    )
    (net (code "77") (name "Net-(U10-Y)") (class "Default")
      (node (ref "U10") (pin "4") (pinfunction "Y_4") (pintype "passive"))
      (node (ref "U9") (pin "1") (pinfunction "A_1") (pintype "passive"))
    )
    (net (code "78") (name "Net-(U11-A)") (class "Default")
      (node (ref "U11") (pin "1") (pinfunction "A_1") (pintype "passive"))
      (node (ref "U9") (pin "4") (pinfunction "Y_4") (pintype "passive"))
    )
    (net (code "79") (name "Net-(U11-B)") (class "Default")
      (node (ref "U11") (pin "2") (pinfunction "B_2") (pintype "passive"))
      (node (ref "U13") (pin "4") (pinfunction "Y_4") (pintype "passive"))
    )
    (net (code "80") (name "Net-(U11-Y)") (class "Default")
      (node (ref "U11") (pin "4") (pinfunction "Y_4") (pintype "passive"))
      (node (ref "U15") (pin "2") (pinfunction "B_2") (pintype "passive"))
    )
    (net (code "81") (name "Net-(U12-Y)") (class "Default")
      (node (ref "U12") (pin "4") (pinfunction "Y_4") (pintype "passive"))
      (node (ref "U13") (pin "2") (pinfunction "B_2") (pintype "passive"))
    )
    (net (code "82") (name "Net-(U13-A)") (class "Default")
      (node (ref "U13") (pin "1") (pinfunction "A_1") (pintype "passive"))
      (node (ref "U14") (pin "4") (pinfunction "Y_4") (pintype "passive"))
    )
    (net (code "83") (name "Net-(U15-A)") (class "Default")
      (node (ref "U15") (pin "1") (pinfunction "A_1") (pintype "passive"))
      (node (ref "U4") (pin "4") (pinfunction "Y_4") (pintype "passive"))
    )
    (net (code "84") (name "unconnected-(K4-Pad1)") (class "Default")
      (node (ref "K4") (pin "1") (pinfunction "1_1") (pintype "passive"))
    )
    (net (code "85") (name "unconnected-(K4-Pad2)") (class "Default")
      (node (ref "K4") (pin "2") (pinfunction "2_2") (pintype "passive"))
    )
    (net (code "86") (name "unconnected-(K4-Pad3)") (class "Default")
      (node (ref "K4") (pin "3") (pinfunction "3_3") (pintype "passive"))
    )
    (net (code "87") (name "unconnected-(K4-Pad4)") (class "Default")
      (node (ref "K4") (pin "4") (pinfunction "4_4") (pintype "passive"))
    )
    (net (code "88") (name "unconnected-(K4-Pad5)") (class "Default")
      (node (ref "K4") (pin "5") (pinfunction "5_5") (pintype "passive"))
    )
    (net (code "89") (name "unconnected-(K4-Pad6)") (class "Default")
      (node (ref "K4") (pin "6") (pinfunction "6_6") (pintype "passive"))
    )
    (net (code "90") (name "unconnected-(K4-Pad7)") (class "Default")
      (node (ref "K4") (pin "7") (pinfunction "7_7") (pintype "passive"))
    )
    (net (code "91") (name "unconnected-(K4-Pad8)") (class "Default")
      (node (ref "K4") (pin "8") (pinfunction "8_8") (pintype "passive"))
    )
    (net (code "92") (name "unconnected-(K4-Pad9)") (class "Default")
      (node (ref "K4") (pin "9") (pinfunction "9_9") (pintype "passive"))
    )
    (net (code "93") (name "unconnected-(K4-Pad10)") (class "Default")
      (node (ref "K4") (pin "10") (pinfunction "10_10") (pintype "passive"))
    )
    (net (code "94") (name "unconnected-(K4-Pad11)") (class "Default")
      (node (ref "K4") (pin "11") (pinfunction "11_11") (pintype "passive"))
    )
    (net (code "95") (name "unconnected-(K4-Pad12)") (class "Default")
      (node (ref "K4") (pin "12") (pinfunction "12_12") (pintype "passive"))
    )
    (net (code "96") (name "unconnected-(K4-Pad13)") (class "Default")
      (node (ref "K4") (pin "13") (pinfunction "13_13") (pintype "passive"))
    )
    (net (code "97") (name "unconnected-(K4-Pad14)") (class "Default")
      (node (ref "K4") (pin "14") (pinfunction "14_14") (pintype "passive"))
    )
    (net (code "98") (name "unconnected-(K4-Pad15)") (class "Default")
      (node (ref "K4") (pin "15") (pinfunction "15_15") (pintype "passive"))
    )
    (net (code "99") (name "unconnected-(K4-Pad16)") (class "Default")
      (node (ref "K4") (pin "16") (pinfunction "16_16") (pintype "passive"))
    )
    (net (code "100") (name "unconnected-(K4-Pad17)") (class "Default")
      (node (ref "K4") (pin "17") (pinfunction "17_17") (pintype "passive"))
    )
    (net (code "101") (name "unconnected-(K4-Pad18)") (class "Default")
      (node (ref "K4") (pin "18") (pinfunction "18_18") (pintype "passive"))
    )
    (net (code "102") (name "unconnected-(K4-Pad19)") (class "Default")
      (node (ref "K4") (pin "19") (pinfunction "19_19") (pintype "passive"))
    )
    (net (code "103") (name "unconnected-(K4-Pad20)") (class "Default")
      (node (ref "K4") (pin "20") (pinfunction "20_20") (pintype "passive"))
    )
    (net (code "104") (name "unconnected-(K4-Pad21)") (class "Default")
      (node (ref "K4") (pin "21") (pinfunction "21_21") (pintype "passive"))
    )
    (net (code "105") (name "unconnected-(K4-Pad22)") (class "Default")
      (node (ref "K4") (pin "22") (pinfunction "22_22") (pintype "passive"))
    )
    (net (code "106") (name "unconnected-(K4-Pad23)") (class "Default")
      (node (ref "K4") (pin "23") (pinfunction "23_23") (pintype "passive"))
    )
    (net (code "107") (name "unconnected-(K4-Pad24)") (class "Default")
      (node (ref "K4") (pin "24") (pinfunction "24_24") (pintype "passive"))
    )
    (net (code "108") (name "unconnected-(K4-Pad25)") (class "Default")
      (node (ref "K4") (pin "25") (pinfunction "25_25") (pintype "passive"))
    )
    (net (code "109") (name "unconnected-(K5-Pad1)") (class "Default")
      (node (ref "K5") (pin "1") (pinfunction "1_1") (pintype "passive"))
    )
    (net (code "110") (name "unconnected-(K5-Pad2)") (class "Default")
      (node (ref "K5") (pin "2") (pinfunction "2_2") (pintype "passive"))
    )
    (net (code "111") (name "unconnected-(K5-Pad3)") (class "Default")
      (node (ref "K5") (pin "3") (pinfunction "3_3") (pintype "passive"))
    )
    (net (code "112") (name "unconnected-(K5-Pad4)") (class "Default")
      (node (ref "K5") (pin "4") (pinfunction "4_4") (pintype "passive"))
    )
    (net (code "113") (name "unconnected-(K5-Pad5)") (class "Default")
      (node (ref "K5") (pin "5") (pinfunction "5_5") (pintype "passive"))
    )
    (net (code "114") (name "unconnected-(K5-Pad6)") (class "Default")
      (node (ref "K5") (pin "6") (pinfunction "6_6") (pintype "passive"))
    )
    (net (code "115") (name "unconnected-(K5-Pad7)") (class "Default")
      (node (ref "K5") (pin "7") (pinfunction "7_7") (pintype "passive"))
    )
    (net (code "116") (name "unconnected-(K5-Pad8)") (class "Default")
      (node (ref "K5") (pin "8") (pinfunction "8_8") (pintype "passive"))
    )
    (net (code "117") (name "unconnected-(K5-Pad9)") (class "Default")
      (node (ref "K5") (pin "9") (pinfunction "9_9") (pintype "passive"))
    )
    (net (code "118") (name "unconnected-(K5-Pad10)") (class "Default")
      (node (ref "K5") (pin "10") (pinfunction "10_10") (pintype "passive"))
    )
    (net (code "119") (name "unconnected-(K5-Pad11)") (class "Default")
      (node (ref "K5") (pin "11") (pinfunction "11_11") (pintype "passive"))
    )
    (net (code "120") (name "unconnected-(K5-Pad12)") (class "Default")
      (node (ref "K5") (pin "12") (pinfunction "12_12") (pintype "passive"))
    )
    (net (code "121") (name "unconnected-(K5-Pad13)") (class "Default")
      (node (ref "K5") (pin "13") (pinfunction "13_13") (pintype "passive"))
    )
    (net (code "122") (name "unconnected-(K5-Pad14)") (class "Default")
      (node (ref "K5") (pin "14") (pinfunction "14_14") (pintype "passive"))
    )
    (net (code "123") (name "unconnected-(K5-Pad15)") (class "Default")
      (node (ref "K5") (pin "15") (pinfunction "15_15") (pintype "passive"))
    )
    (net (code "124") (name "unconnected-(K5-Pad16)") (class "Default")
      (node (ref "K5") (pin "16") (pinfunction "16_16") (pintype "passive"))
    )
    (net (code "125") (name "unconnected-(K5-Pad17)") (class "Default")
      (node (ref "K5") (pin "17") (pinfunction "17_17") (pintype "passive"))
    )
    (net (code "126") (name "unconnected-(K5-Pad18)") (class "Default")
      (node (ref "K5") (pin "18") (pinfunction "18_18") (pintype "passive"))
    )
    (net (code "127") (name "unconnected-(K5-Pad19)") (class "Default")
      (node (ref "K5") (pin "19") (pinfunction "19_19") (pintype "passive"))
    )
    (net (code "128") (name "unconnected-(K5-Pad20)") (class "Default")
      (node (ref "K5") (pin "20") (pinfunction "20_20") (pintype "passive"))
    )
    (net (code "129") (name "unconnected-(K5-Pad21)") (class "Default")
      (node (ref "K5") (pin "21") (pinfunction "21_21") (pintype "passive"))
    )
    (net (code "130") (name "unconnected-(K5-Pad22)") (class "Default")
      (node (ref "K5") (pin "22") (pinfunction "22_22") (pintype "passive"))
    )
    (net (code "131") (name "unconnected-(K5-Pad23)") (class "Default")
      (node (ref "K5") (pin "23") (pinfunction "23_23") (pintype "passive"))
    )
    (net (code "132") (name "unconnected-(K5-Pad24)") (class "Default")
      (node (ref "K5") (pin "24") (pinfunction "24_24") (pintype "passive"))
    )
    (net (code "133") (name "unconnected-(K5-Pad25)") (class "Default")
      (node (ref "K5") (pin "25") (pinfunction "25_25") (pintype "passive"))
    )
  )
)
